# MPHS-RFM69C.net
KiCad netlist of a schematic drawn in EAGLE
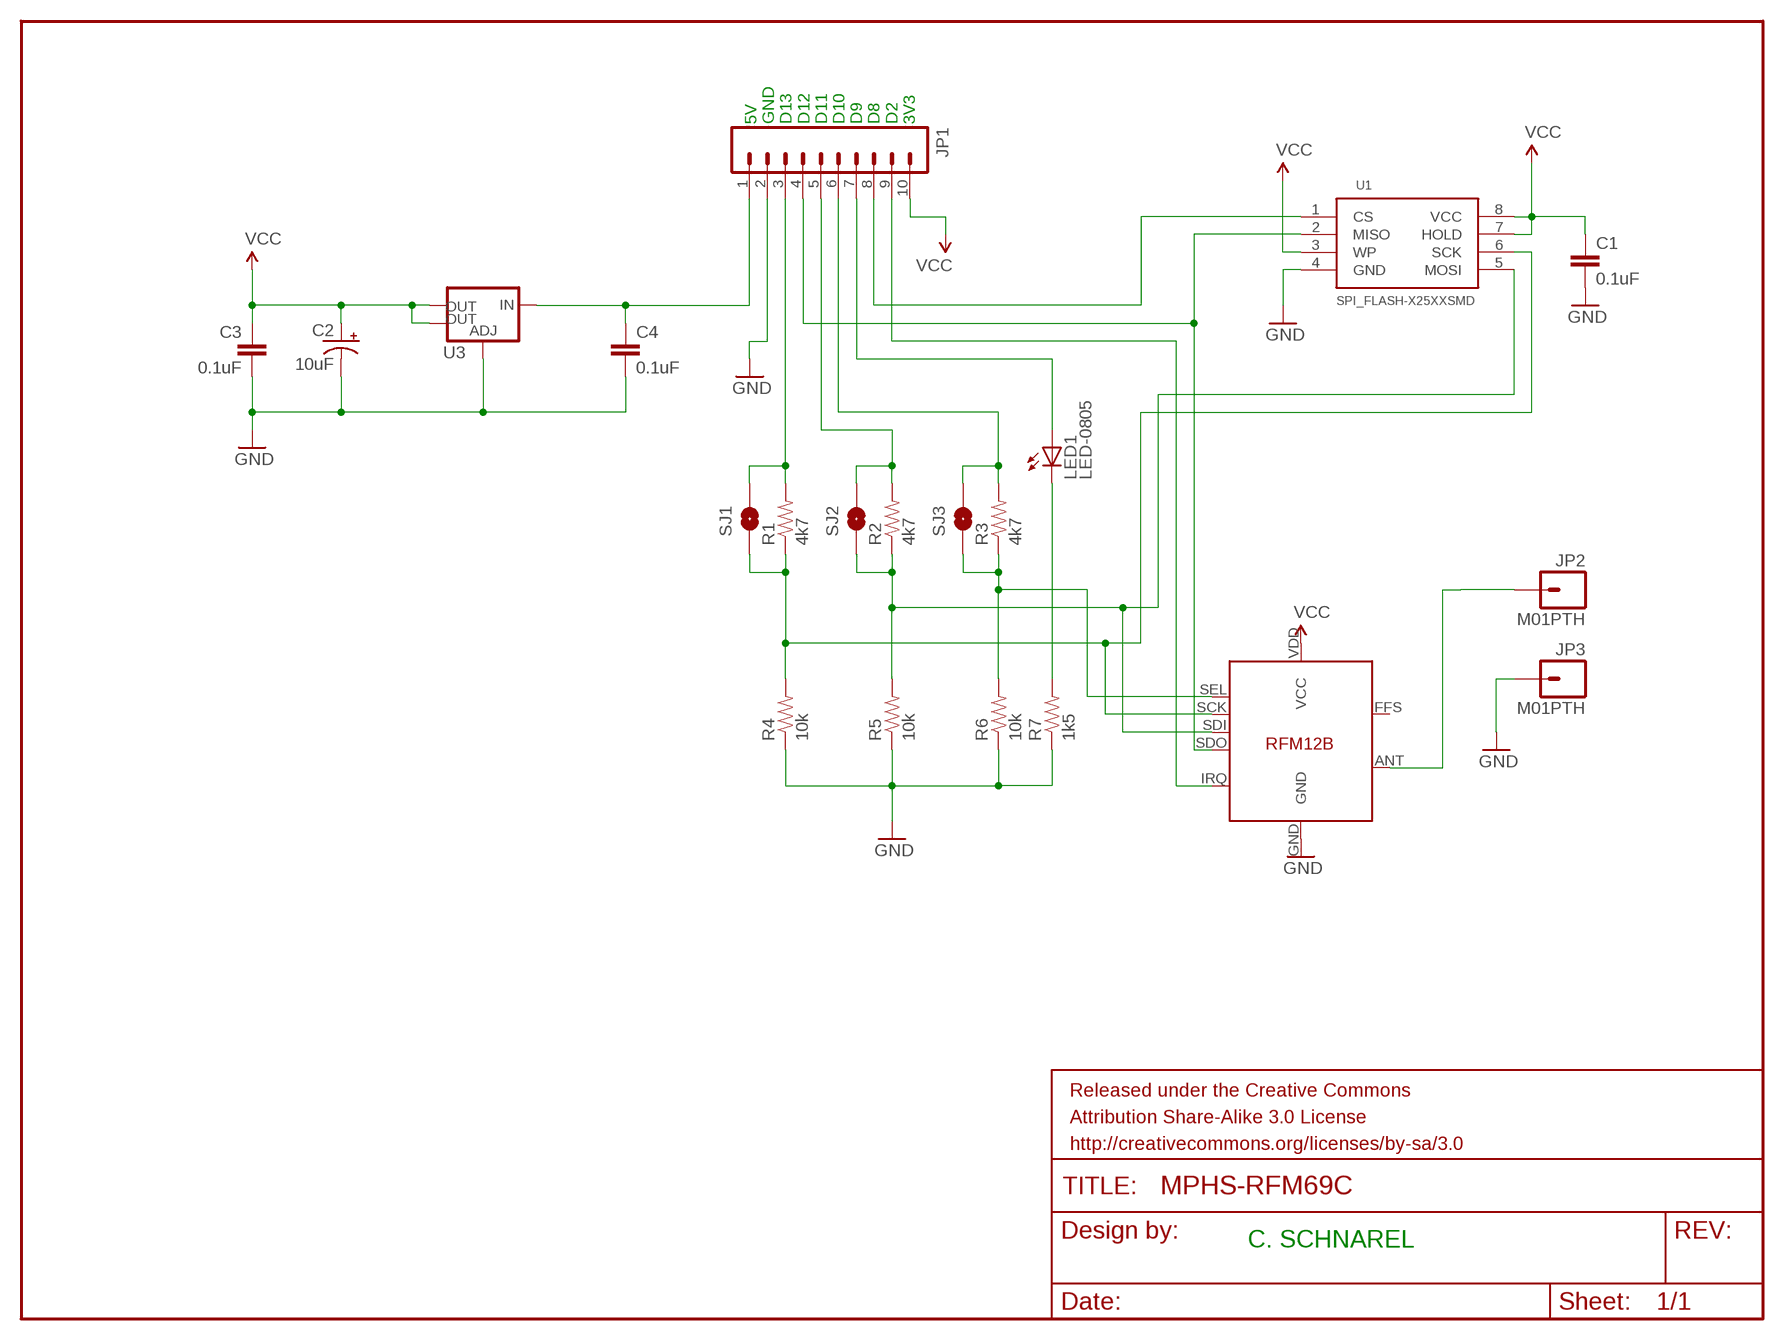
[diagram p0: schematic, sheet 1]

(export (version "E")
  (design (tool "Eeschema 10.0.6"))
  (components
    (comp (ref "C1")
      (value "0.1uF")
      (footprint "eagle-import:0805")
      (libsource (lib "eagle-import") (part "CAP0805"))
    )
    (comp (ref "C2")
      (value "10uF")
      (footprint "eagle-import:0805-POL")
      (libsource (lib "eagle-import") (part "CAP_POL0805"))
    )
    (comp (ref "C3")
      (value "0.1uF")
      (footprint "eagle-import:0805")
      (libsource (lib "eagle-import") (part "CAP0805"))
    )
    (comp (ref "C4")
      (value "0.1uF")
      (footprint "eagle-import:0805")
      (libsource (lib "eagle-import") (part "CAP0805"))
    )
    (comp (ref "FRAME1")
      (value "FRAME-LETTER")
      (footprint "eagle-import:CREATIVE_COMMONS")
      (libsource (lib "eagle-import") (part "FRAME-LETTER"))
    )
    (comp (ref "JP1")
      (value "M10\"")
      (footprint "eagle-import:1X10")
      (libsource (lib "eagle-import") (part "M10{dblquote}"))
    )
    (comp (ref "JP2")
      (value "M01PTH")
      (footprint "eagle-import:1X01")
      (libsource (lib "eagle-import") (part "M01PTH"))
    )
    (comp (ref "JP3")
      (value "M01PTH")
      (footprint "eagle-import:1X01")
      (libsource (lib "eagle-import") (part "M01PTH"))
    )
    (comp (ref "LED1")
      (value "LED-0805")
      (footprint "eagle-import:0805-LED")
      (libsource (lib "eagle-import") (part "LED-0805"))
    )
    (comp (ref "R1")
      (value "4k7")
      (footprint "eagle-import:0805")
      (libsource (lib "eagle-import") (part "RESISTOR0805-RES"))
    )
    (comp (ref "R2")
      (value "4k7")
      (footprint "eagle-import:0805")
      (libsource (lib "eagle-import") (part "RESISTOR0805-RES"))
    )
    (comp (ref "R3")
      (value "4k7")
      (footprint "eagle-import:0805")
      (libsource (lib "eagle-import") (part "RESISTOR0805-RES"))
    )
    (comp (ref "R4")
      (value "10k")
      (footprint "eagle-import:0805")
      (libsource (lib "eagle-import") (part "RESISTOR0805-RES"))
    )
    (comp (ref "R5")
      (value "10k")
      (footprint "eagle-import:0805")
      (libsource (lib "eagle-import") (part "RESISTOR0805-RES"))
    )
    (comp (ref "R6")
      (value "10k")
      (footprint "eagle-import:0805")
      (libsource (lib "eagle-import") (part "RESISTOR0805-RES"))
    )
    (comp (ref "R7")
      (value "1k5")
      (footprint "eagle-import:0805")
      (libsource (lib "eagle-import") (part "RESISTOR0805-RES"))
    )
    (comp (ref "SJ1")
      (value "SOLDERJUMPERNO")
      (footprint "eagle-import:SJ_2S-NO")
      (libsource (lib "eagle-import") (part "SOLDERJUMPERNO"))
    )
    (comp (ref "SJ2")
      (value "SOLDERJUMPERNO")
      (footprint "eagle-import:SJ_2S-NO")
      (libsource (lib "eagle-import") (part "SOLDERJUMPERNO"))
    )
    (comp (ref "SJ3")
      (value "SOLDERJUMPERNO")
      (footprint "eagle-import:SJ_2S-NO")
      (libsource (lib "eagle-import") (part "SOLDERJUMPERNO"))
    )
    (comp (ref "U$1")
      (value "RFM12B")
      (footprint "eagle-import:RFM12B")
      (libsource (lib "eagle-import") (part "RFM12B"))
    )
    (comp (ref "U1")
      (value "SPI_FLASH-X25XXSMD")
      (footprint "eagle-import:SO08")
      (libsource (lib "eagle-import") (part "SPI_FLASH-X25XXSMD"))
    )
    (comp (ref "U3")
      (value "V_REG_LM1117SOT223")
      (footprint "eagle-import:SOT223")
      (libsource (lib "eagle-import") (part "V_REG_LM1117SOT223"))
    )
  )
  (nets
    (net (code "1") (name "GND") (class "Default")
      (node (ref "C1") (pin "2") (pinfunction "2_2") (pintype "passive"))
      (node (ref "C2") (pin "2") (pinfunction "-_2") (pintype "passive"))
      (node (ref "C3") (pin "2") (pinfunction "2_2") (pintype "passive"))
      (node (ref "C4") (pin "2") (pinfunction "2_2") (pintype "passive"))
      (node (ref "JP1") (pin "2") (pinfunction "2_2") (pintype "passive"))
      (node (ref "JP3") (pin "1") (pinfunction "1_1") (pintype "passive"))
      (node (ref "R4") (pin "1") (pinfunction "1_1") (pintype "passive"))
      (node (ref "R5") (pin "1") (pinfunction "1_1") (pintype "passive"))
      (node (ref "R6") (pin "1") (pinfunction "1_1") (pintype "passive"))
      (node (ref "R7") (pin "1") (pinfunction "1_1") (pintype "passive"))
      (node (ref "U$1") (pin "GND") (pinfunction "GND_GND") (pintype "power_in"))
      (node (ref "U1") (pin "4") (pinfunction "GND_4") (pintype "bidirectional"))
      (node (ref "U3") (pin "1") (pinfunction "ADJ_1") (pintype "input"))
    )
    (net (code "2") (name "Net-(JP1-Pad3)") (class "Default")
      (node (ref "JP1") (pin "3") (pinfunction "3_3") (pintype "passive"))
      (node (ref "R1") (pin "2") (pinfunction "2_2") (pintype "passive"))
      (node (ref "SJ1") (pin "2") (pinfunction "2_2") (pintype "passive"))
    )
    (net (code "3") (name "Net-(JP1-Pad5)") (class "Default")
      (node (ref "JP1") (pin "5") (pinfunction "5_5") (pintype "passive"))
      (node (ref "R2") (pin "2") (pinfunction "2_2") (pintype "passive"))
      (node (ref "SJ2") (pin "2") (pinfunction "2_2") (pintype "passive"))
    )
    (net (code "4") (name "Net-(JP1-Pad6)") (class "Default")
      (node (ref "JP1") (pin "6") (pinfunction "6_6") (pintype "passive"))
      (node (ref "R3") (pin "2") (pinfunction "2_2") (pintype "passive"))
      (node (ref "SJ3") (pin "2") (pinfunction "2_2") (pintype "passive"))
    )
    (net (code "5") (name "Net-(JP1-Pad7)") (class "Default")
      (node (ref "JP1") (pin "7") (pinfunction "7_7") (pintype "passive"))
      (node (ref "LED1") (pin "A") (pinfunction "A_A") (pintype "passive"))
    )
    (net (code "6") (name "Net-(JP1-Pad9)") (class "Default")
      (node (ref "JP1") (pin "9") (pinfunction "9_9") (pintype "passive"))
      (node (ref "U$1") (pin "IRQ") (pinfunction "IRQ_IRQ") (pintype "open_collector"))
    )
    (net (code "7") (name "Net-(JP2-Pad1)") (class "Default")
      (node (ref "JP2") (pin "1") (pinfunction "1_1") (pintype "passive"))
      (node (ref "U$1") (pin "ANT") (pinfunction "ANT_ANT") (pintype "passive"))
    )
    (net (code "8") (name "Net-(LED1-PadC)") (class "Default")
      (node (ref "LED1") (pin "C") (pinfunction "C_C") (pintype "passive"))
      (node (ref "R7") (pin "2") (pinfunction "2_2") (pintype "passive"))
    )
    (net (code "9") (name "Net-(R3-Pad1)") (class "Default")
      (node (ref "R3") (pin "1") (pinfunction "1_1") (pintype "passive"))
      (node (ref "R6") (pin "2") (pinfunction "2_2") (pintype "passive"))
      (node (ref "SJ3") (pin "1") (pinfunction "1_1") (pintype "passive"))
      (node (ref "U$1") (pin "SEL") (pinfunction "SEL_SEL") (pintype "input"))
    )
    (net (code "10") (name "Net-(U1-CS)") (class "Default")
      (node (ref "JP1") (pin "8") (pinfunction "8_8") (pintype "passive"))
      (node (ref "U1") (pin "1") (pinfunction "CS_1") (pintype "bidirectional"))
    )
    (net (code "11") (name "Net-(U1-MISO)") (class "Default")
      (node (ref "JP1") (pin "4") (pinfunction "4_4") (pintype "passive"))
      (node (ref "U$1") (pin "SDO") (pinfunction "SDO_SDO") (pintype "output"))
      (node (ref "U1") (pin "2") (pinfunction "MISO_2") (pintype "bidirectional"))
    )
    (net (code "12") (name "Net-(U1-MOSI)") (class "Default")
      (node (ref "R2") (pin "1") (pinfunction "1_1") (pintype "passive"))
      (node (ref "R5") (pin "2") (pinfunction "2_2") (pintype "passive"))
      (node (ref "SJ2") (pin "1") (pinfunction "1_1") (pintype "passive"))
      (node (ref "U$1") (pin "SDI") (pinfunction "SDI_SDI") (pintype "input"))
      (node (ref "U1") (pin "5") (pinfunction "MOSI_5") (pintype "bidirectional"))
    )
    (net (code "13") (name "Net-(U1-SCK)") (class "Default")
      (node (ref "R1") (pin "1") (pinfunction "1_1") (pintype "passive"))
      (node (ref "R4") (pin "2") (pinfunction "2_2") (pintype "passive"))
      (node (ref "SJ1") (pin "1") (pinfunction "1_1") (pintype "passive"))
      (node (ref "U$1") (pin "SCK") (pinfunction "SCK_SCK") (pintype "input"))
      (node (ref "U1") (pin "6") (pinfunction "SCK_6") (pintype "bidirectional"))
    )
    (net (code "14") (name "Net-(U3-IN)") (class "Default")
      (node (ref "C4") (pin "1") (pinfunction "1_1") (pintype "passive"))
      (node (ref "JP1") (pin "1") (pinfunction "1_1") (pintype "passive"))
      (node (ref "U3") (pin "3") (pinfunction "IN_3") (pintype "input"))
    )
    (net (code "15") (name "VCC") (class "Default")
      (node (ref "C1") (pin "1") (pinfunction "1_1") (pintype "passive"))
      (node (ref "C2") (pin "1") (pinfunction "+_1") (pintype "passive"))
      (node (ref "C3") (pin "1") (pinfunction "1_1") (pintype "passive"))
      (node (ref "JP1") (pin "10") (pinfunction "10_10") (pintype "passive"))
      (node (ref "U$1") (pin "VDD") (pinfunction "VCC_VDD") (pintype "power_in"))
      (node (ref "U1") (pin "3") (pinfunction "WP_3") (pintype "bidirectional"))
      (node (ref "U1") (pin "7") (pinfunction "HOLD_7") (pintype "bidirectional"))
      (node (ref "U1") (pin "8") (pinfunction "VCC_8") (pintype "bidirectional"))
      (node (ref "U3") (pin "2") (pinfunction "OUT_2") (pintype "output"))
      (node (ref "U3") (pin "4") (pinfunction "OUT_4") (pintype "output"))
    )
    (net (code "16") (name "unconnected-(U$1-PadFFS)") (class "Default")
      (node (ref "U$1") (pin "FFS") (pinfunction "FFS_FFS") (pintype "bidirectional"))
    )
  )
)
